# PZEM-004T.net
KiCad netlist of a schematic drawn in Altium Designer
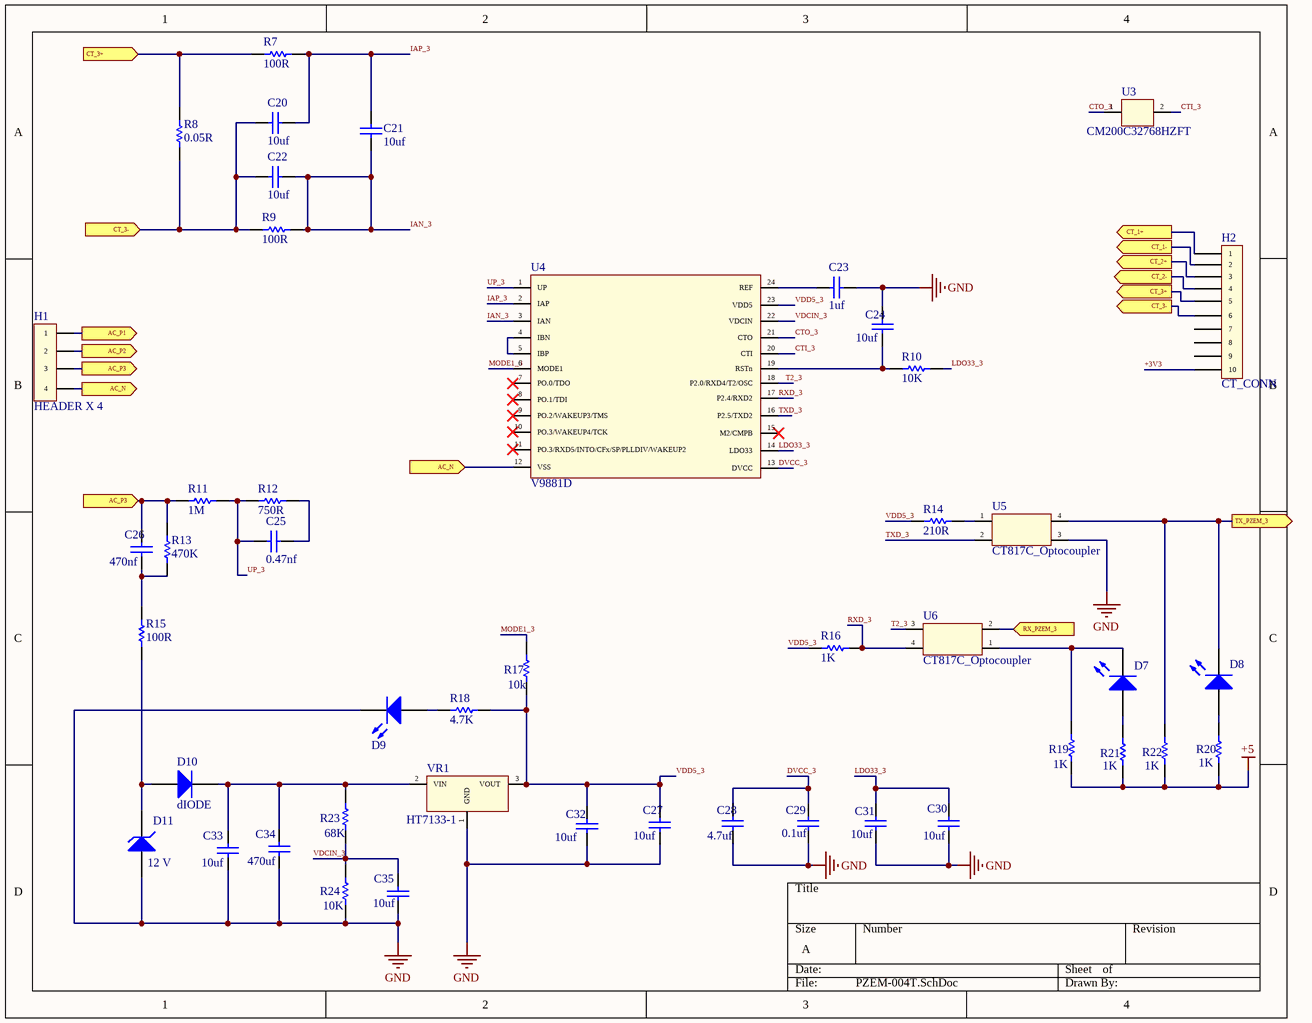
[diagram p0: PZEM-004T.SchDoc]

(export (version "E")
  (design (tool "Eeschema 10.0.6"))
  (components
    (comp (ref "C20")
      (value "10uf")
      (footprint "CAPC1005X55N")
      (description "CAP CER 10UF 6.3V X5R 0402")
      (fields (field (name "MANUFACTURER") "Murata Electronics"))
      (libsource (lib "PZEM-004T") (part "capacitor"))
    )
    (comp (ref "C21")
      (value "10uf")
      (footprint "CAPC1005X55N")
      (description "CAP CER 10UF 6.3V X5R 0402")
      (fields (field (name "MANUFACTURER") "Murata Electronics"))
      (libsource (lib "PZEM-004T") (part "capacitor"))
    )
    (comp (ref "C22")
      (value "10uf")
      (footprint "CAPC1005X55N")
      (description "CAP CER 10UF 6.3V X5R 0402")
      (fields (field (name "MANUFACTURER") "Murata Electronics"))
      (libsource (lib "PZEM-004T") (part "capacitor"))
    )
    (comp (ref "C23")
      (value "1uf")
      (footprint "CAPC1005X55N")
      (description "CAP CER 10UF 6.3V X5R 0402")
      (fields (field (name "MANUFACTURER") "Murata Electronics"))
      (libsource (lib "PZEM-004T") (part "capacitor"))
    )
    (comp (ref "C24")
      (value "10uf")
      (footprint "CAPC1005X55N")
      (description "CAP CER 10UF 6.3V X5R 0402")
      (fields (field (name "MANUFACTURER") "Murata Electronics"))
      (libsource (lib "PZEM-004T") (part "capacitor"))
    )
    (comp (ref "C25")
      (value "0.47nf")
      (footprint "CAPRR1250W60L1530T500H1150")
      (description "CAP CER 10UF 6.3V X5R 0402")
      (fields (field (name "MANUFACTURER") "Murata Electronics"))
      (libsource (lib "PZEM-004T") (part "capacitor"))
    )
    (comp (ref "C26")
      (value "470nf")
      (footprint "CAPC1005X55N")
      (description "CAP CER 10UF 6.3V X5R 0402")
      (fields (field (name "MANUFACTURER") "Murata Electronics"))
      (libsource (lib "PZEM-004T") (part "capacitor"))
    )
    (comp (ref "C27")
      (value "10uf")
      (footprint "CAPC1005X55N")
      (description "CAP CER 10UF 6.3V X5R 0402")
      (fields (field (name "MANUFACTURER") "Murata Electronics"))
      (libsource (lib "PZEM-004T") (part "capacitor"))
    )
    (comp (ref "C28")
      (value "4.7uf")
      (footprint "CAPC1005X55N")
      (description "CAP CER 10UF 6.3V X5R 0402")
      (fields (field (name "MANUFACTURER") "Murata Electronics"))
      (libsource (lib "PZEM-004T") (part "capacitor"))
    )
    (comp (ref "C29")
      (value "0.1uf")
      (footprint "CAPC1005X55N")
      (description "CAP CER 10UF 6.3V X5R 0402")
      (fields (field (name "MANUFACTURER") "Murata Electronics"))
      (libsource (lib "PZEM-004T") (part "capacitor"))
    )
    (comp (ref "C30")
      (value "10uf")
      (footprint "CAPC1005X55N")
      (description "CAP CER 10UF 6.3V X5R 0402")
      (fields (field (name "MANUFACTURER") "Murata Electronics"))
      (libsource (lib "PZEM-004T") (part "capacitor"))
    )
    (comp (ref "C31")
      (value "10uf")
      (footprint "CAPC1005X55N")
      (description "CAP CER 10UF 6.3V X5R 0402")
      (fields (field (name "MANUFACTURER") "Murata Electronics"))
      (libsource (lib "PZEM-004T") (part "capacitor"))
    )
    (comp (ref "C32")
      (value "10uf")
      (footprint "CAPC1005X55N")
      (description "CAP CER 10UF 6.3V X5R 0402")
      (fields (field (name "MANUFACTURER") "Murata Electronics"))
      (libsource (lib "PZEM-004T") (part "capacitor"))
    )
    (comp (ref "C33")
      (value "10uf")
      (footprint "CAPC1005X55N")
      (description "CAP CER 10UF 6.3V X5R 0402")
      (fields (field (name "MANUFACTURER") "Murata Electronics"))
      (libsource (lib "PZEM-004T") (part "capacitor"))
    )
    (comp (ref "C34")
      (value "470uf")
      (footprint "CAPC1005X55N")
      (description "CAP CER 10UF 6.3V X5R 0402")
      (fields (field (name "MANUFACTURER") "Murata Electronics"))
      (libsource (lib "PZEM-004T") (part "capacitor"))
    )
    (comp (ref "C35")
      (value "10uf")
      (footprint "CAPC1005X55N")
      (description "CAP CER 10UF 6.3V X5R 0402")
      (fields (field (name "MANUFACTURER") "Murata Electronics"))
      (libsource (lib "PZEM-004T") (part "capacitor"))
    )
    (comp (ref "D7")
      (value "LED_")
      (footprint "WL-SMCW_0603_150060xx8x000")
      (description "LED GREEN CLEAR 0805 SMD")
      (fields (field (name "MANUFACTURER") "Lumex Opto/Components Inc."))
      (libsource (lib "PZEM-004T") (part "LED_"))
    )
    (comp (ref "D8")
      (value "LED_")
      (footprint "WL-SMCW_0603_150060xx8x000")
      (description "LED GREEN CLEAR 0805 SMD")
      (fields (field (name "MANUFACTURER") "Lumex Opto/Components Inc."))
      (libsource (lib "PZEM-004T") (part "LED_"))
    )
    (comp (ref "D9")
      (value "LED_")
      (footprint "WL-SMCW_0603_150060xx8x000")
      (description "LED GREEN CLEAR 0805 SMD")
      (fields (field (name "MANUFACTURER") "Lumex Opto/Components Inc."))
      (libsource (lib "PZEM-004T") (part "LED_"))
    )
    (comp (ref "D10")
      (value "dIODE")
      (footprint "WL-SMCW_0603_150060xx8x000")
      (libsource (lib "PZEM-004T") (part "dIODE"))
    )
    (comp (ref "D11")
      (value "12 V")
      (footprint "SMA_DIO-L")
      (description "Zener Diode 12 V 1 W ±5% Surface Mount SMA")
      (fields (field (name "MANUFACTURER") "Diodes Incorporated"))
      (libsource (lib "PZEM-004T") (part "ZENER"))
    )
    (comp (ref "H1")
      (value "HEADER X 4")
      (footprint "PHOENIX_1757268")
      (description "4 X PIN HEADER FOR THE VOLTAGE CONNECTOR OF 3 PZEM")
      (libsource (lib "PZEM-004T") (part "HEADER X 4"))
    )
    (comp (ref "H2")
      (value "CT_CONN")
      (footprint "10 Pin terminal block")
      (description "6 X PIN HEADER FOR THE CURRENT TRANSFORMER CONNECTIONS")
      (libsource (lib "PZEM-004T") (part "CT_CONN"))
    )
    (comp (ref "R7")
      (value "100R")
      (footprint "RESISTOR")
      (description "RES 10K OHM 5% 1/4W 1206")
      (fields (field (name "MANUFACTURER") "TE Connectivity Passive Product"))
      (libsource (lib "PZEM-004T") (part "Resistor"))
    )
    (comp (ref "R8")
      (value "0.05R")
      (footprint "RESAD700W45L350D185")
      (description "RES 10K OHM 5% 1/4W 1206")
      (fields (field (name "MANUFACTURER") "TE Connectivity Passive Product"))
      (libsource (lib "PZEM-004T") (part "Resistor"))
    )
    (comp (ref "R9")
      (value "100R")
      (footprint "RESISTOR")
      (description "RES 10K OHM 5% 1/4W 1206")
      (fields (field (name "MANUFACTURER") "TE Connectivity Passive Product"))
      (libsource (lib "PZEM-004T") (part "Resistor"))
    )
    (comp (ref "R10")
      (value "10K")
      (footprint "RESISTOR")
      (description "RES 10K OHM 5% 1/4W 1206")
      (fields (field (name "MANUFACTURER") "TE Connectivity Passive Product"))
      (libsource (lib "PZEM-004T") (part "Resistor"))
    )
    (comp (ref "R11")
      (value "1M")
      (footprint "RES_0603")
      (description "RES 10K OHM 5% 1/4W 1206")
      (fields (field (name "MANUFACTURER") "TE Connectivity Passive Product"))
      (libsource (lib "PZEM-004T") (part "Resistor"))
    )
    (comp (ref "R12")
      (value "750R")
      (footprint "RESISTOR")
      (description "RES 10K OHM 5% 1/4W 1206")
      (fields (field (name "MANUFACTURER") "TE Connectivity Passive Product"))
      (libsource (lib "PZEM-004T") (part "Resistor"))
    )
    (comp (ref "R13")
      (value "470K")
      (footprint "RESISTOR")
      (description "RES 10K OHM 5% 1/4W 1206")
      (fields (field (name "MANUFACTURER") "TE Connectivity Passive Product"))
      (libsource (lib "PZEM-004T") (part "Resistor"))
    )
    (comp (ref "R14")
      (value "210R")
      (footprint "RESISTOR")
      (description "RES 10K OHM 5% 1/4W 1206")
      (fields (field (name "MANUFACTURER") "TE Connectivity Passive Product"))
      (libsource (lib "PZEM-004T") (part "Resistor"))
    )
    (comp (ref "R15")
      (value "100R")
      (footprint "RESISTOR")
      (description "RES 10K OHM 5% 1/4W 1206")
      (fields (field (name "MANUFACTURER") "TE Connectivity Passive Product"))
      (libsource (lib "PZEM-004T") (part "Resistor"))
    )
    (comp (ref "R16")
      (value "1K")
      (footprint "RESISTOR")
      (description "RES 10K OHM 5% 1/4W 1206")
      (fields (field (name "MANUFACTURER") "TE Connectivity Passive Product"))
      (libsource (lib "PZEM-004T") (part "Resistor"))
    )
    (comp (ref "R17")
      (value "10k")
      (footprint "RESISTOR")
      (description "RES 10K OHM 5% 1/4W 1206")
      (fields (field (name "MANUFACTURER") "TE Connectivity Passive Product"))
      (libsource (lib "PZEM-004T") (part "Resistor"))
    )
    (comp (ref "R18")
      (value "4.7K")
      (footprint "RESISTOR")
      (description "RES 10K OHM 5% 1/4W 1206")
      (fields (field (name "MANUFACTURER") "TE Connectivity Passive Product"))
      (libsource (lib "PZEM-004T") (part "Resistor"))
    )
    (comp (ref "R19")
      (value "1K")
      (footprint "RESISTOR")
      (description "RES 10K OHM 5% 1/4W 1206")
      (fields (field (name "MANUFACTURER") "TE Connectivity Passive Product"))
      (libsource (lib "PZEM-004T") (part "Resistor"))
    )
    (comp (ref "R20")
      (value "1K")
      (footprint "RESISTOR")
      (description "RES 10K OHM 5% 1/4W 1206")
      (fields (field (name "MANUFACTURER") "TE Connectivity Passive Product"))
      (libsource (lib "PZEM-004T") (part "Resistor"))
    )
    (comp (ref "R21")
      (value "1K")
      (footprint "RESISTOR")
      (description "RES 10K OHM 5% 1/4W 1206")
      (fields (field (name "MANUFACTURER") "TE Connectivity Passive Product"))
      (libsource (lib "PZEM-004T") (part "Resistor"))
    )
    (comp (ref "R22")
      (value "1K")
      (footprint "RESISTOR")
      (description "RES 10K OHM 5% 1/4W 1206")
      (fields (field (name "MANUFACTURER") "TE Connectivity Passive Product"))
      (libsource (lib "PZEM-004T") (part "Resistor"))
    )
    (comp (ref "R23")
      (value "68K")
      (footprint "RESISTOR")
      (description "RES 10K OHM 5% 1/4W 1206")
      (fields (field (name "MANUFACTURER") "TE Connectivity Passive Product"))
      (libsource (lib "PZEM-004T") (part "Resistor"))
    )
    (comp (ref "R24")
      (value "10K")
      (footprint "RESISTOR")
      (description "RES 10K OHM 5% 1/4W 1206")
      (fields (field (name "MANUFACTURER") "TE Connectivity Passive Product"))
      (libsource (lib "PZEM-004T") (part "Resistor"))
    )
    (comp (ref "U3")
      (value "CM200C32768HZFT")
      (footprint "XTAL_CM8V-T1A-32.768KHZ-12.5PF-20PPM-TA-QA")
      (description "32.768 kHz ±5ppm Crystal 12.5pF 50 kOhms 4-SOJ, 5.50mm pitch")
      (fields (field (name "MANUFACTURER") "Citizen Finedevice Co Ltd"))
      (libsource (lib "PZEM-004T") (part "CM200C32768HZFT"))
    )
    (comp (ref "U4")
      (value "V9881D")
      (footprint "SOP24 - duplicate")
      (description "V9881D SSOP24 Three-phase Multifunctional Metering Chip Energy Metering V9881")
      (libsource (lib "PZEM-004T") (part "V9881D"))
    )
    (comp (ref "U5")
      (value "CT817C_Optocoupler")
      (footprint "SOP4")
      (fields (field (name "MANUFACTURER") "CT Micro International"))
      (libsource (lib "PZEM-004T") (part "CT817C_Optocoupler"))
    )
    (comp (ref "U6")
      (value "CT817C_Optocoupler")
      (footprint "SOP4")
      (fields (field (name "MANUFACTURER") "CT Micro International"))
      (libsource (lib "") (part "CT817C_Optocoupler_1"))
    )
    (comp (ref "VR1")
      (value "HT7133-1")
      (footprint "SOP3")
      (description "Linear Voltage Regulator IC Positive Fixed 1 Output 100mA SOT-89-3")
      (fields (field (name "MANUFACTURER") "UMW"))
      (libsource (lib "PZEM-004T") (part "HT7133-1"))
    )
  )
  (nets
    (net (code "1") (name "+5") (class "Default")
      (node (ref "R19") (pin "1") (pinfunction "1_1") (pintype "passive"))
      (node (ref "R20") (pin "1") (pinfunction "1_1") (pintype "passive"))
      (node (ref "R21") (pin "1") (pinfunction "1_1") (pintype "passive"))
      (node (ref "R22") (pin "1") (pinfunction "1_1") (pintype "passive"))
    )
    (net (code "2") (name "/+3V3") (class "Default")
      (node (ref "H2") (pin "10") (pinfunction "10_10") (pintype "passive"))
    )
    (net (code "3") (name "/AC_N") (class "Default")
      (node (ref "H1") (pin "4") (pinfunction "4_4") (pintype "passive"))
      (node (ref "U4") (pin "12") (pinfunction "VSS_12") (pintype "passive"))
    )
    (net (code "4") (name "/AC_P1") (class "Default")
      (node (ref "H1") (pin "1") (pinfunction "1_1") (pintype "passive"))
    )
    (net (code "5") (name "/AC_P2") (class "Default")
      (node (ref "H1") (pin "2") (pinfunction "2_2") (pintype "passive"))
    )
    (net (code "6") (name "/AC_P3") (class "Default")
      (node (ref "C26") (pin "2") (pinfunction "2_2") (pintype "passive"))
      (node (ref "H1") (pin "3") (pinfunction "3_3") (pintype "passive"))
      (node (ref "R11") (pin "1") (pinfunction "1_1") (pintype "passive"))
      (node (ref "R13") (pin "1") (pinfunction "1_1") (pintype "passive"))
    )
    (net (code "7") (name "/CTI_3") (class "Default")
      (node (ref "U3") (pin "2") (pinfunction "2_2") (pintype "passive"))
      (node (ref "U4") (pin "20") (pinfunction "CTI_20") (pintype "passive"))
    )
    (net (code "8") (name "/CTO_3") (class "Default")
      (node (ref "U3") (pin "1") (pinfunction "1_1") (pintype "passive"))
      (node (ref "U4") (pin "21") (pinfunction "CTO_21") (pintype "passive"))
    )
    (net (code "9") (name "/CT_1+") (class "Default")
      (node (ref "H2") (pin "1") (pinfunction "1_1") (pintype "passive"))
    )
    (net (code "10") (name "/CT_1-") (class "Default")
      (node (ref "H2") (pin "2") (pinfunction "2_2") (pintype "passive"))
    )
    (net (code "11") (name "/CT_2+") (class "Default")
      (node (ref "H2") (pin "3") (pinfunction "3_3") (pintype "passive"))
    )
    (net (code "12") (name "/CT_2-") (class "Default")
      (node (ref "H2") (pin "4") (pinfunction "4_4") (pintype "passive"))
    )
    (net (code "13") (name "/CT_3+") (class "Default")
      (node (ref "H2") (pin "5") (pinfunction "5_5") (pintype "passive"))
      (node (ref "R7") (pin "2") (pinfunction "2_2") (pintype "passive"))
      (node (ref "R8") (pin "1") (pinfunction "1_1") (pintype "passive"))
    )
    (net (code "14") (name "/CT_3-") (class "Default")
      (node (ref "C20") (pin "2") (pinfunction "2_2") (pintype "passive"))
      (node (ref "C22") (pin "2") (pinfunction "2_2") (pintype "passive"))
      (node (ref "H2") (pin "6") (pinfunction "6_6") (pintype "passive"))
      (node (ref "R8") (pin "2") (pinfunction "2_2") (pintype "passive"))
      (node (ref "R9") (pin "2") (pinfunction "2_2") (pintype "passive"))
    )
    (net (code "15") (name "/DVCC_3") (class "Default")
      (node (ref "C28") (pin "2") (pinfunction "2_2") (pintype "passive"))
      (node (ref "C29") (pin "2") (pinfunction "2_2") (pintype "passive"))
      (node (ref "U4") (pin "13") (pinfunction "DVCC_13") (pintype "passive"))
    )
    (net (code "16") (name "/IAN_3") (class "Default")
      (node (ref "C21") (pin "1") (pinfunction "1_1") (pintype "passive"))
      (node (ref "C22") (pin "1") (pinfunction "1_1") (pintype "passive"))
      (node (ref "R9") (pin "1") (pinfunction "1_1") (pintype "passive"))
      (node (ref "U4") (pin "3") (pinfunction "IAN_3") (pintype "passive"))
    )
    (net (code "17") (name "/IAP_3") (class "Default")
      (node (ref "C20") (pin "1") (pinfunction "1_1") (pintype "passive"))
      (node (ref "C21") (pin "2") (pinfunction "2_2") (pintype "passive"))
      (node (ref "R7") (pin "1") (pinfunction "1_1") (pintype "passive"))
      (node (ref "U4") (pin "2") (pinfunction "IAP_2") (pintype "passive"))
    )
    (net (code "18") (name "/LDO33_3") (class "Default")
      (node (ref "C30") (pin "2") (pinfunction "2_2") (pintype "passive"))
      (node (ref "C31") (pin "2") (pinfunction "2_2") (pintype "passive"))
      (node (ref "R10") (pin "2") (pinfunction "2_2") (pintype "passive"))
      (node (ref "U4") (pin "14") (pinfunction "LDO33_14") (pintype "passive"))
    )
    (net (code "19") (name "/MODE1_3") (class "Default")
      (node (ref "R17") (pin "2") (pinfunction "2_2") (pintype "passive"))
      (node (ref "U4") (pin "6") (pinfunction "MODE1_6") (pintype "passive"))
    )
    (net (code "20") (name "/RXD_3") (class "Default")
      (node (ref "R16") (pin "1") (pinfunction "1_1") (pintype "passive"))
      (node (ref "U4") (pin "17") (pinfunction "P2.4/RXD2_17") (pintype "passive"))
      (node (ref "U6") (pin "4") (pinfunction "COLLECTOR_4") (pintype "passive"))
    )
    (net (code "21") (name "/RX_PZEM_3") (class "Default")
      (node (ref "U6") (pin "2") (pinfunction "CATHODE_2") (pintype "passive"))
    )
    (net (code "22") (name "/T2_3") (class "Default")
      (node (ref "U4") (pin "18") (pinfunction "P2.0/RXD4/T2/OSC_18") (pintype "passive"))
      (node (ref "U6") (pin "3") (pinfunction "EMITTER_3") (pintype "passive"))
    )
    (net (code "23") (name "/TXD_3") (class "Default")
      (node (ref "U4") (pin "16") (pinfunction "P2.5/TXD2_16") (pintype "passive"))
      (node (ref "U5") (pin "2") (pinfunction "CATHODE_2") (pintype "passive"))
    )
    (net (code "24") (name "/TX_PZEM_3") (class "Default")
      (node (ref "D8") (pin "2") (pinfunction "K_2") (pintype "passive"))
      (node (ref "R22") (pin "2") (pinfunction "2_2") (pintype "passive"))
      (node (ref "U5") (pin "4") (pinfunction "COLLECTOR_4") (pintype "passive"))
    )
    (net (code "25") (name "/UP_3") (class "Default")
      (node (ref "C25") (pin "2") (pinfunction "2_2") (pintype "passive"))
      (node (ref "R11") (pin "2") (pinfunction "2_2") (pintype "passive"))
      (node (ref "R12") (pin "1") (pinfunction "1_1") (pintype "passive"))
      (node (ref "U4") (pin "1") (pinfunction "UP_1") (pintype "passive"))
    )
    (net (code "26") (name "/VDCIN_3") (class "Default")
      (node (ref "C35") (pin "2") (pinfunction "2_2") (pintype "passive"))
      (node (ref "R23") (pin "1") (pinfunction "1_1") (pintype "passive"))
      (node (ref "R24") (pin "2") (pinfunction "2_2") (pintype "passive"))
      (node (ref "U4") (pin "22") (pinfunction "VDCIN_22") (pintype "passive"))
    )
    (net (code "27") (name "/VDD5_3") (class "Default")
      (node (ref "C27") (pin "2") (pinfunction "2_2") (pintype "passive"))
      (node (ref "C32") (pin "2") (pinfunction "2_2") (pintype "passive"))
      (node (ref "R14") (pin "2") (pinfunction "2_2") (pintype "passive"))
      (node (ref "R16") (pin "2") (pinfunction "2_2") (pintype "passive"))
      (node (ref "R17") (pin "1") (pinfunction "1_1") (pintype "passive"))
      (node (ref "R18") (pin "1") (pinfunction "1_1") (pintype "passive"))
      (node (ref "U4") (pin "23") (pinfunction "VDD5_23") (pintype "passive"))
      (node (ref "VR1") (pin "3") (pinfunction "VOUT_3") (pintype "passive"))
    )
    (net (code "28") (name "GND") (class "Default")
      (node (ref "C23") (pin "2") (pinfunction "2_2") (pintype "passive"))
      (node (ref "C24") (pin "2") (pinfunction "2_2") (pintype "passive"))
      (node (ref "C27") (pin "1") (pinfunction "1_1") (pintype "passive"))
      (node (ref "C28") (pin "1") (pinfunction "1_1") (pintype "passive"))
      (node (ref "C29") (pin "1") (pinfunction "1_1") (pintype "passive"))
      (node (ref "C30") (pin "1") (pinfunction "1_1") (pintype "passive"))
      (node (ref "C31") (pin "1") (pinfunction "1_1") (pintype "passive"))
      (node (ref "C32") (pin "1") (pinfunction "1_1") (pintype "passive"))
      (node (ref "C33") (pin "1") (pinfunction "1_1") (pintype "passive"))
      (node (ref "C34") (pin "1") (pinfunction "1_1") (pintype "passive"))
      (node (ref "C35") (pin "1") (pinfunction "1_1") (pintype "passive"))
      (node (ref "D11") (pin "1") (pinfunction "A_1") (pintype "passive"))
      (node (ref "D9") (pin "2") (pinfunction "K_2") (pintype "passive"))
      (node (ref "R24") (pin "1") (pinfunction "1_1") (pintype "passive"))
      (node (ref "U5") (pin "3") (pinfunction "EMITTER_3") (pintype "passive"))
      (node (ref "VR1") (pin "1") (pinfunction "GND_1") (pintype "passive"))
    )
    (net (code "29") (name "Net-(C25-Pad1)") (class "Default")
      (node (ref "C25") (pin "1") (pinfunction "1_1") (pintype "passive"))
      (node (ref "R12") (pin "2") (pinfunction "2_2") (pintype "passive"))
    )
    (net (code "30") (name "Net-(C26-Pad1)") (class "Default")
      (node (ref "C26") (pin "1") (pinfunction "1_1") (pintype "passive"))
      (node (ref "R13") (pin "2") (pinfunction "2_2") (pintype "passive"))
      (node (ref "R15") (pin "1") (pinfunction "1_1") (pintype "passive"))
    )
    (net (code "31") (name "Net-(D7-A)") (class "Default")
      (node (ref "D7") (pin "1") (pinfunction "A_1") (pintype "passive"))
      (node (ref "R21") (pin "2") (pinfunction "2_2") (pintype "passive"))
    )
    (net (code "32") (name "Net-(D7-K)") (class "Default")
      (node (ref "D7") (pin "2") (pinfunction "K_2") (pintype "passive"))
      (node (ref "R19") (pin "2") (pinfunction "2_2") (pintype "passive"))
      (node (ref "U6") (pin "1") (pinfunction "ANODE_1") (pintype "passive"))
    )
    (net (code "33") (name "Net-(D8-A)") (class "Default")
      (node (ref "D8") (pin "1") (pinfunction "A_1") (pintype "passive"))
      (node (ref "R20") (pin "2") (pinfunction "2_2") (pintype "passive"))
    )
    (net (code "34") (name "Net-(D9-A)") (class "Default")
      (node (ref "D9") (pin "1") (pinfunction "A_1") (pintype "passive"))
      (node (ref "R18") (pin "2") (pinfunction "2_2") (pintype "passive"))
    )
    (net (code "35") (name "Net-(D10-A)") (class "Default")
      (node (ref "D10") (pin "1") (pinfunction "A_1") (pintype "passive"))
      (node (ref "D11") (pin "2") (pinfunction "K_2") (pintype "passive"))
      (node (ref "R15") (pin "2") (pinfunction "2_2") (pintype "passive"))
    )
    (net (code "36") (name "Net-(D10-K)") (class "Default")
      (node (ref "C33") (pin "2") (pinfunction "2_2") (pintype "passive"))
      (node (ref "C34") (pin "2") (pinfunction "2_2") (pintype "passive"))
      (node (ref "D10") (pin "2") (pinfunction "K_2") (pintype "passive"))
      (node (ref "R23") (pin "2") (pinfunction "2_2") (pintype "passive"))
      (node (ref "VR1") (pin "2") (pinfunction "VIN_2") (pintype "passive"))
    )
    (net (code "37") (name "Net-(U4-IBN)") (class "Default")
      (node (ref "U4") (pin "4") (pinfunction "IBN_4") (pintype "passive"))
      (node (ref "U4") (pin "5") (pinfunction "IBP_5") (pintype "passive"))
    )
    (net (code "38") (name "Net-(U4-REF)") (class "Default")
      (node (ref "C23") (pin "1") (pinfunction "1_1") (pintype "passive"))
      (node (ref "U4") (pin "24") (pinfunction "REF_24") (pintype "passive"))
    )
    (net (code "39") (name "Net-(U4-RSTn)") (class "Default")
      (node (ref "C24") (pin "1") (pinfunction "1_1") (pintype "passive"))
      (node (ref "R10") (pin "1") (pinfunction "1_1") (pintype "passive"))
      (node (ref "U4") (pin "19") (pinfunction "RSTn_19") (pintype "passive"))
    )
    (net (code "40") (name "Net-(U5-ANODE)") (class "Default")
      (node (ref "R14") (pin "1") (pinfunction "1_1") (pintype "passive"))
      (node (ref "U5") (pin "1") (pinfunction "ANODE_1") (pintype "passive"))
    )
    (net (code "41") (name "unconnected-(H2-Pad7)") (class "Default")
      (node (ref "H2") (pin "7") (pinfunction "7_7") (pintype "passive"))
    )
    (net (code "42") (name "unconnected-(H2-Pad8)") (class "Default")
      (node (ref "H2") (pin "8") (pinfunction "8_8") (pintype "passive"))
    )
    (net (code "43") (name "unconnected-(H2-Pad9)") (class "Default")
      (node (ref "H2") (pin "9") (pinfunction "9_9") (pintype "passive"))
    )
    (net (code "44") (name "unconnected-(U4-M2{slash}CMPB-Pad15)") (class "Default")
      (node (ref "U4") (pin "15") (pinfunction "M2/CMPB_15") (pintype "passive+no_connect"))
    )
    (net (code "45") (name "unconnected-(U4-PO.0{slash}TDO-Pad7)") (class "Default")
      (node (ref "U4") (pin "7") (pinfunction "PO.0/TDO_7") (pintype "passive+no_connect"))
    )
    (net (code "46") (name "unconnected-(U4-PO.1{slash}TDI-Pad8)") (class "Default")
      (node (ref "U4") (pin "8") (pinfunction "PO.1/TDI_8") (pintype "passive+no_connect"))
    )
    (net (code "47") (name "unconnected-(U4-PO.2{slash}WAKEUP3{slash}TMS-Pad9)") (class "Default")
      (node (ref "U4") (pin "9") (pinfunction "PO.2/WAKEUP3/TMS_9") (pintype "passive+no_connect"))
    )
    (net (code "48") (name "unconnected-(U4-PO.3{slash}RXD5{slash}INTO{slash}CFx{slash}SP{slash}PLLDIV{slash}WAKEUP2-Pad11)") (class "Default")
      (node (ref "U4") (pin "11") (pinfunction "PO.3/RXD5/INTO/CFx/SP/PLLDIV/WAKEUP2_11") (pintype "passive+no_connect"))
    )
    (net (code "49") (name "unconnected-(U4-PO.3{slash}WAKEUP4{slash}TCK-Pad10)") (class "Default")
      (node (ref "U4") (pin "10") (pinfunction "PO.3/WAKEUP4/TCK_10") (pintype "passive+no_connect"))
    )
  )
)
